# BadUSB.net
KiCad netlist of a schematic drawn in Altium Designer
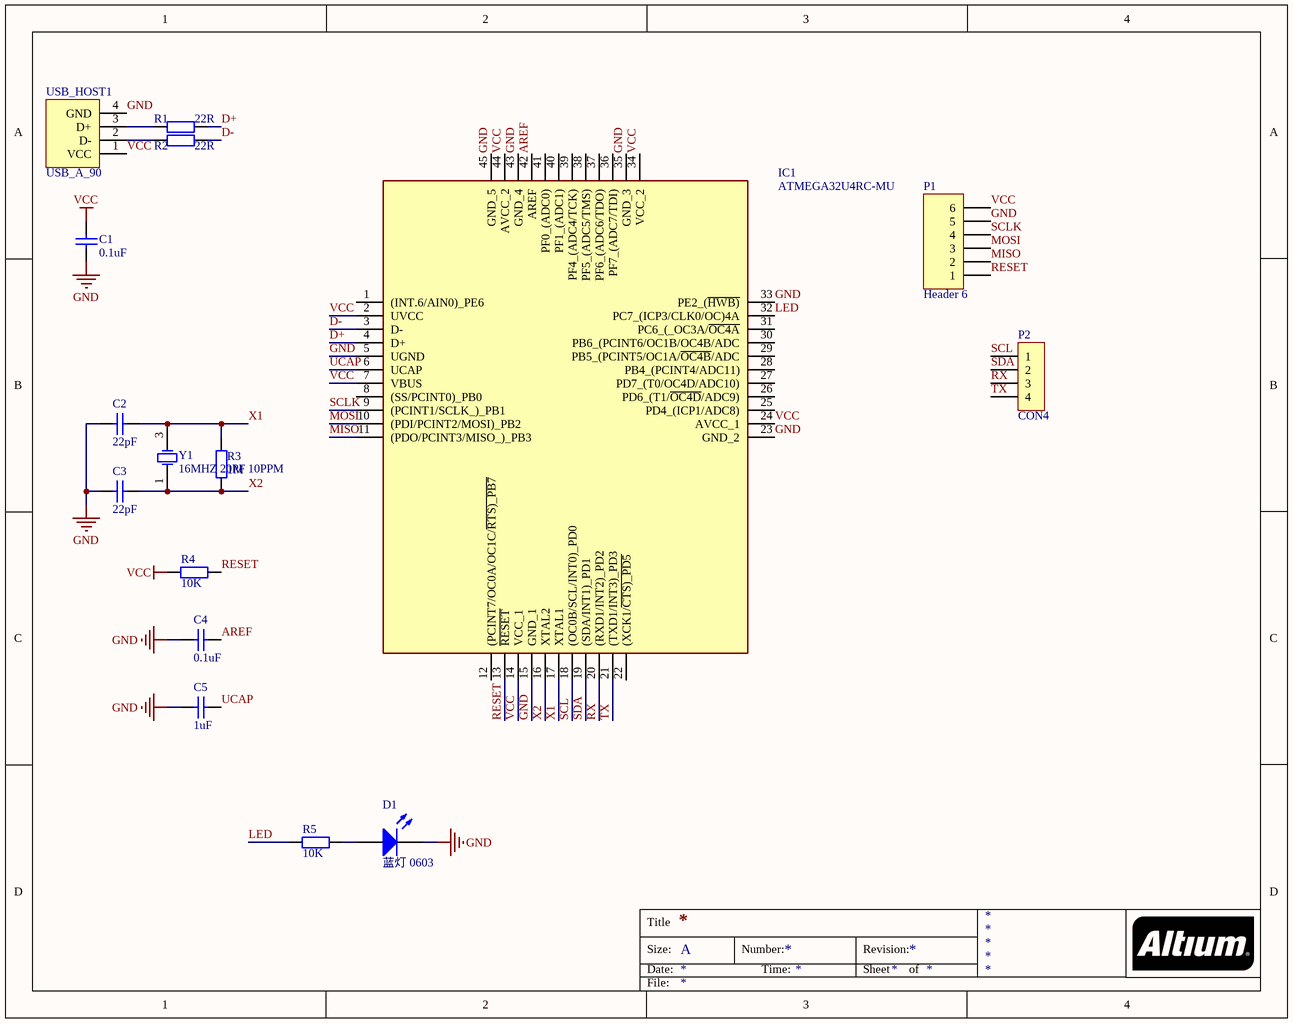
[diagram p0: BadUSB.SchDoc]

(export (version "E")
  (design (tool "Eeschema 10.0.6"))
  (components
    (comp (ref "C1")
      (value "0.1uF")
      (footprint "C 0603_L")
      (description "贴片电容")
      (libsource (lib "嘉立创") (part "0402 1.0uF (105) 10% 25V"))
    )
    (comp (ref "C2")
      (value "22pF")
      (footprint "C 0603_L")
      (description "贴片电容")
      (libsource (lib "嘉立创") (part "0402 1.0uF (105) 10% 25V"))
    )
    (comp (ref "C3")
      (value "22pF")
      (footprint "C 0603_L")
      (description "贴片电容")
      (libsource (lib "嘉立创") (part "0402 1.0uF (105) 10% 25V"))
    )
    (comp (ref "C4")
      (value "0.1uF")
      (footprint "C 0603_L")
      (description "贴片电容")
      (libsource (lib "嘉立创") (part "0402 1.0uF (105) 10% 25V"))
    )
    (comp (ref "C5")
      (value "1uF")
      (footprint "C 0603_L")
      (description "贴片电容")
      (libsource (lib "嘉立创") (part "0402 1.0uF (105) 10% 25V"))
    )
    (comp (ref "D1")
      (value "蓝灯 0603")
      (footprint "0603_LED_S1")
      (description "发光二极管")
      (libsource (lib "嘉立创") (part "0603 蓝灯"))
    )
    (comp (ref "IC1")
      (value "ATMEGA32U4RC-MU")
      (footprint "SamacSys:QFN50P700X700X100-45N-D")
      (description "Integrated Circuit")
      (fields (field (name "MOUSER PART NUMBER") "556-ATMEGA32U4RC-MU"))
      (libsource (lib "*") (part "ATMEGA32U4RC-MU"))
    )
    (comp (ref "P1")
      (value "Header 6")
      (footprint "HDR2.54-LI-6P")
      (description "Header, 6-Pin")
      (fields (field (name "PUBLISHER") "Altium Limited"))
      (libsource (lib "3D_library") (part "Header 6"))
    )
    (comp (ref "P2")
      (value "CON4")
      (footprint "HDR2.54-LI-4P")
      (description "Connector")
      (libsource (lib "插件") (part "CON4"))
    )
    (comp (ref "R1")
      (value "22R")
      (footprint "R 0603_L")
      (description "贴片电阻")
      (libsource (lib "嘉立创") (part "0402 0Ω (0R0) 1%"))
    )
    (comp (ref "R2")
      (value "22R")
      (footprint "R 0603_L")
      (description "贴片电阻")
      (libsource (lib "嘉立创") (part "0402 0Ω (0R0) 1%"))
    )
    (comp (ref "R3")
      (value "1M")
      (footprint "R 0603_L")
      (description "贴片电阻")
      (libsource (lib "") (part "0402 0Ω (0R0) 1%_1"))
    )
    (comp (ref "R4")
      (value "10K")
      (footprint "R 0603_L")
      (description "贴片电阻")
      (libsource (lib "嘉立创") (part "0402 0Ω (0R0) 1%"))
    )
    (comp (ref "R5")
      (value "10K")
      (footprint "R 0603_L")
      (description "贴片电阻")
      (libsource (lib "嘉立创") (part "0402 0Ω (0R0) 1%"))
    )
    (comp (ref "USB_HOST1")
      (value "USB_A_90")
      (footprint "USB_A/P_B")
      (libsource (lib "haidai") (part "USB_A_90"))
    )
    (comp (ref "Y1")
      (value "16MHZ 20PF 10PPM")
      (footprint "OSC 3225-4P")
      (description "贴片晶振")
      (libsource (lib "嘉立创") (part "SMD-3225_4P  12MHZ 20PF 10PPM"))
    )
  )
  (nets
    (net (code "1") (name "/AREF") (class "Default")
      (node (ref "C4") (pin "1") (pinfunction "1_1") (pintype "passive"))
      (node (ref "IC1") (pin "42") (pinfunction "AREF_42") (pintype "passive"))
    )
    (net (code "2") (name "/D+") (class "Default")
      (node (ref "IC1") (pin "4") (pinfunction "D+_4") (pintype "passive"))
      (node (ref "R1") (pin "1") (pinfunction "1_1") (pintype "passive"))
    )
    (net (code "3") (name "/D-") (class "Default")
      (node (ref "IC1") (pin "3") (pinfunction "D-_3") (pintype "passive"))
      (node (ref "R2") (pin "1") (pinfunction "1_1") (pintype "passive"))
    )
    (net (code "4") (name "/LED") (class "Default")
      (node (ref "IC1") (pin "32") (pinfunction "PC7_(ICP3/CLK0/OC)4A_32") (pintype "passive"))
      (node (ref "R5") (pin "2") (pinfunction "2_2") (pintype "passive"))
    )
    (net (code "5") (name "/MISO") (class "Default")
      (node (ref "IC1") (pin "11") (pinfunction "(PDO/PCINT3/MISO_)_PB3_11") (pintype "passive"))
      (node (ref "P1") (pin "2") (pinfunction "2_2") (pintype "passive"))
    )
    (net (code "6") (name "/MOSI") (class "Default")
      (node (ref "IC1") (pin "10") (pinfunction "(PDI/PCINT2/MOSI)_PB2_10") (pintype "passive"))
      (node (ref "P1") (pin "3") (pinfunction "3_3") (pintype "passive"))
    )
    (net (code "7") (name "/RESET") (class "Default")
      (node (ref "IC1") (pin "13") (pinfunction "~{RESET}_13") (pintype "passive"))
      (node (ref "P1") (pin "1") (pinfunction "1_1") (pintype "passive"))
      (node (ref "R4") (pin "1") (pinfunction "1_1") (pintype "passive"))
    )
    (net (code "8") (name "/RX") (class "Default")
      (node (ref "IC1") (pin "20") (pinfunction "(RXD1/INT2)_PD2_20") (pintype "passive"))
      (node (ref "P2") (pin "3") (pinfunction "3_3") (pintype "passive"))
    )
    (net (code "9") (name "/SCL") (class "Default")
      (node (ref "IC1") (pin "18") (pinfunction "(OC0B/SCL/INT0)_PD0_18") (pintype "passive"))
      (node (ref "P2") (pin "1") (pinfunction "1_1") (pintype "passive"))
    )
    (net (code "10") (name "/SCLK") (class "Default")
      (node (ref "IC1") (pin "9") (pinfunction "(PCINT1/SCLK_)_PB1_9") (pintype "passive"))
      (node (ref "P1") (pin "4") (pinfunction "4_4") (pintype "passive"))
    )
    (net (code "11") (name "/SDA") (class "Default")
      (node (ref "IC1") (pin "19") (pinfunction "(SDA/INT1)_PD1_19") (pintype "passive"))
      (node (ref "P2") (pin "2") (pinfunction "2_2") (pintype "passive"))
    )
    (net (code "12") (name "/TX") (class "Default")
      (node (ref "IC1") (pin "21") (pinfunction "(TXD1/INT3)_PD3_21") (pintype "passive"))
      (node (ref "P2") (pin "4") (pinfunction "4_4") (pintype "passive"))
    )
    (net (code "13") (name "/UCAP") (class "Default")
      (node (ref "C5") (pin "1") (pinfunction "1_1") (pintype "passive"))
      (node (ref "IC1") (pin "6") (pinfunction "UCAP_6") (pintype "passive"))
    )
    (net (code "14") (name "/X1") (class "Default")
      (node (ref "C2") (pin "1") (pinfunction "1_1") (pintype "passive"))
      (node (ref "IC1") (pin "17") (pinfunction "XTAL1_17") (pintype "passive"))
      (node (ref "R3") (pin "2") (pinfunction "2_2") (pintype "passive"))
      (node (ref "Y1") (pin "3") (pinfunction "OSC2_3") (pintype "passive"))
    )
    (net (code "15") (name "/X2") (class "Default")
      (node (ref "C3") (pin "1") (pinfunction "1_1") (pintype "passive"))
      (node (ref "IC1") (pin "16") (pinfunction "XTAL2_16") (pintype "passive"))
      (node (ref "R3") (pin "1") (pinfunction "1_1") (pintype "passive"))
      (node (ref "Y1") (pin "1") (pinfunction "OSC1_1") (pintype "passive"))
    )
    (net (code "16") (name "GND") (class "Default")
      (node (ref "C1") (pin "1") (pinfunction "1_1") (pintype "passive"))
      (node (ref "C2") (pin "2") (pinfunction "2_2") (pintype "passive"))
      (node (ref "C3") (pin "2") (pinfunction "2_2") (pintype "passive"))
      (node (ref "C4") (pin "2") (pinfunction "2_2") (pintype "passive"))
      (node (ref "C5") (pin "2") (pinfunction "2_2") (pintype "passive"))
      (node (ref "D1") (pin "K") (pinfunction "K_K") (pintype "passive"))
      (node (ref "IC1") (pin "15") (pinfunction "GND_1_15") (pintype "passive"))
      (node (ref "IC1") (pin "23") (pinfunction "GND_2_23") (pintype "passive"))
      (node (ref "IC1") (pin "33") (pinfunction "PE2_(~{HWB)}_33") (pintype "passive"))
      (node (ref "IC1") (pin "35") (pinfunction "GND_3_35") (pintype "passive"))
      (node (ref "IC1") (pin "43") (pinfunction "GND_4_43") (pintype "passive"))
      (node (ref "IC1") (pin "45") (pinfunction "GND_5_45") (pintype "passive"))
      (node (ref "IC1") (pin "5") (pinfunction "UGND_5") (pintype "passive"))
      (node (ref "P1") (pin "5") (pinfunction "5_5") (pintype "passive"))
      (node (ref "USB_HOST1") (pin "4") (pinfunction "GND_4") (pintype "passive"))
    )
    (net (code "17") (name "Net-(D1-PadA)") (class "Default")
      (node (ref "D1") (pin "A") (pinfunction "A_A") (pintype "passive"))
      (node (ref "R5") (pin "1") (pinfunction "1_1") (pintype "passive"))
    )
    (net (code "18") (name "Net-(USB_HOST1-D+)") (class "Default")
      (node (ref "R1") (pin "2") (pinfunction "2_2") (pintype "passive"))
      (node (ref "USB_HOST1") (pin "3") (pinfunction "D+_3") (pintype "passive"))
    )
    (net (code "19") (name "Net-(USB_HOST1-D-)") (class "Default")
      (node (ref "R2") (pin "2") (pinfunction "2_2") (pintype "passive"))
      (node (ref "USB_HOST1") (pin "2") (pinfunction "D-_2") (pintype "passive"))
    )
    (net (code "20") (name "VCC") (class "Default")
      (node (ref "C1") (pin "2") (pinfunction "2_2") (pintype "passive"))
      (node (ref "IC1") (pin "14") (pinfunction "VCC_1_14") (pintype "passive"))
      (node (ref "IC1") (pin "2") (pinfunction "UVCC_2") (pintype "passive"))
      (node (ref "IC1") (pin "24") (pinfunction "AVCC_1_24") (pintype "passive"))
      (node (ref "IC1") (pin "34") (pinfunction "VCC_2_34") (pintype "passive"))
      (node (ref "IC1") (pin "44") (pinfunction "AVCC_2_44") (pintype "passive"))
      (node (ref "IC1") (pin "7") (pinfunction "VBUS_7") (pintype "passive"))
      (node (ref "P1") (pin "6") (pinfunction "6_6") (pintype "passive"))
      (node (ref "R4") (pin "2") (pinfunction "2_2") (pintype "passive"))
      (node (ref "USB_HOST1") (pin "1") (pinfunction "VCC_1") (pintype "passive"))
    )
    (net (code "21") (name "unconnected-(IC1-(INT.6{slash}AIN0)_PE6-Pad1)") (class "Default")
      (node (ref "IC1") (pin "1") (pinfunction "(INT.6/AIN0)_PE6_1") (pintype "passive"))
    )
    (net (code "22") (name "unconnected-(IC1-(PCINT7{slash}OC0A{slash}OC1C{slash}~{RTS)_PB7}-Pad12)") (class "Default")
      (node (ref "IC1") (pin "12") (pinfunction "(PCINT7/OC0A/OC1C/~{RTS)_PB7}_12") (pintype "passive"))
    )
    (net (code "23") (name "unconnected-(IC1-(SS{slash}PCINT0)_PB0-Pad8)") (class "Default")
      (node (ref "IC1") (pin "8") (pinfunction "(SS/PCINT0)_PB0_8") (pintype "passive"))
    )
    (net (code "24") (name "unconnected-(IC1-(XCK1{slash}~{CTS)_PD5}-Pad22)") (class "Default")
      (node (ref "IC1") (pin "22") (pinfunction "(XCK1/~{CTS)_PD5}_22") (pintype "passive"))
    )
    (net (code "25") (name "unconnected-(IC1-PB4_(PCINT4{slash}ADC11)-Pad28)") (class "Default")
      (node (ref "IC1") (pin "28") (pinfunction "PB4_(PCINT4/ADC11)_28") (pintype "passive"))
    )
    (net (code "26") (name "unconnected-(IC1-PB5_(PCINT5{slash}OC1A{slash}~{OC4B}{slash}ADC-Pad29)") (class "Default")
      (node (ref "IC1") (pin "29") (pinfunction "PB5_(PCINT5/OC1A/~{OC4B}/ADC_29") (pintype "passive"))
    )
    (net (code "27") (name "unconnected-(IC1-PB6_(PCINT6{slash}OC1B{slash}OC4B{slash}ADC-Pad30)") (class "Default")
      (node (ref "IC1") (pin "30") (pinfunction "PB6_(PCINT6/OC1B/OC4B/ADC_30") (pintype "passive"))
    )
    (net (code "28") (name "unconnected-(IC1-PC6_(_OC3A{slash}~{OC4A}-Pad31)") (class "Default")
      (node (ref "IC1") (pin "31") (pinfunction "PC6_(_OC3A/~{OC4A}_31") (pintype "passive"))
    )
    (net (code "29") (name "unconnected-(IC1-PD4_(ICP1{slash}ADC8)-Pad25)") (class "Default")
      (node (ref "IC1") (pin "25") (pinfunction "PD4_(ICP1/ADC8)_25") (pintype "passive"))
    )
    (net (code "30") (name "unconnected-(IC1-PD6_(T1{slash}~{OC4D}{slash}ADC9)-Pad26)") (class "Default")
      (node (ref "IC1") (pin "26") (pinfunction "PD6_(T1/~{OC4D}/ADC9)_26") (pintype "passive"))
    )
    (net (code "31") (name "unconnected-(IC1-PD7_(T0{slash}OC4D{slash}ADC10)-Pad27)") (class "Default")
      (node (ref "IC1") (pin "27") (pinfunction "PD7_(T0/OC4D/ADC10)_27") (pintype "passive"))
    )
    (net (code "32") (name "unconnected-(IC1-PF0_(ADC0)-Pad41)") (class "Default")
      (node (ref "IC1") (pin "41") (pinfunction "PF0_(ADC0)_41") (pintype "passive"))
    )
    (net (code "33") (name "unconnected-(IC1-PF1_(ADC1)-Pad40)") (class "Default")
      (node (ref "IC1") (pin "40") (pinfunction "PF1_(ADC1)_40") (pintype "passive"))
    )
    (net (code "34") (name "unconnected-(IC1-PF4_(ADC4{slash}TCK)-Pad39)") (class "Default")
      (node (ref "IC1") (pin "39") (pinfunction "PF4_(ADC4/TCK)_39") (pintype "passive"))
    )
    (net (code "35") (name "unconnected-(IC1-PF5_(ADC5{slash}TMS)-Pad38)") (class "Default")
      (node (ref "IC1") (pin "38") (pinfunction "PF5_(ADC5/TMS)_38") (pintype "passive"))
    )
    (net (code "36") (name "unconnected-(IC1-PF6_(ADC6{slash}TDO)-Pad37)") (class "Default")
      (node (ref "IC1") (pin "37") (pinfunction "PF6_(ADC6/TDO)_37") (pintype "passive"))
    )
    (net (code "37") (name "unconnected-(IC1-PF7_(ADC7{slash}TDI)-Pad36)") (class "Default")
      (node (ref "IC1") (pin "36") (pinfunction "PF7_(ADC7/TDI)_36") (pintype "passive"))
    )
  )
)
